# 103_OLED.net
KiCad netlist of a schematic drawn in Altium Designer
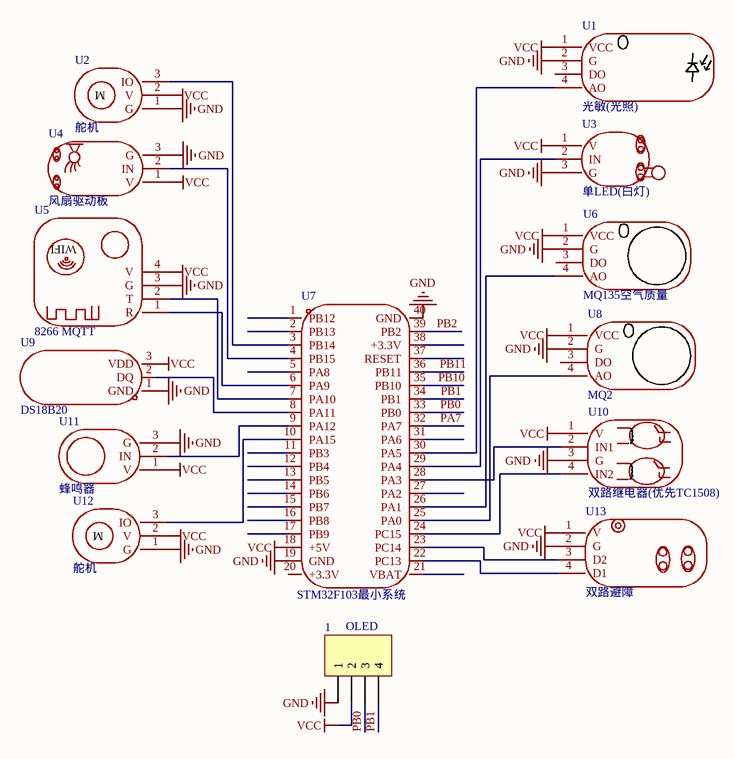
[diagram p0: 103+OLED原理图.SCHDOC]

(export (version "E")
  (design (tool "Eeschema 10.0.6"))
  (components
    (comp (ref "1")
      (value "OLED")
      (footprint "HDR1X4")
      (description "Header, 4-Pin")
      (fields (field (name "PUBLISHER") "Altium Limited"))
      (libsource (lib "Miscellaneous Connectors") (part "Header 4"))
    )
    (comp (ref "U1")
      (value "光敏(光照)")
      (footprint "HDR1X4")
      (description "NCH")
      (libsource (lib "1毕设原理图库") (part "光敏(光照)"))
    )
    (comp (ref "U2")
      (value "舵机")
      (footprint "HDR1X3")
      (description "NBI")
      (libsource (lib "1毕设原理图库") (part "舵机"))
    )
    (comp (ref "U3") (value "单LED(白灯)") (description "NBC") (libsource (lib "1毕设原理图库") (part "单LED(白灯)")))
    (comp (ref "U4")
      (value "风扇驱动板")
      (footprint "HDR1X3")
      (description "NCI")
      (libsource (lib "1毕设原理图库") (part "风扇驱动板"))
    )
    (comp (ref "U5")
      (value "8266 MQTT")
      (footprint "HDR1X4")
      (description "NCB")
      (libsource (lib "1毕设原理图库") (part "8266 MQTT"))
    )
    (comp (ref "U6") (value "MQ135空气质量") (description "NAZM") (libsource (lib "1毕设原理图库") (part "MQ135空气质量")))
    (comp (ref "U7")
      (value "STM32F103最小系统")
      (fields (field (name "MANUFACTURER PART") "LCKFB-DKX-STM32F103C8T6"))
      (libsource (lib "altium-import") (part "root_0_LCKFB-DKX-STM32F103C8T6_"))
    )
    (comp (ref "U8")
      (value "MQ2")
      (footprint "HDR1X4")
      (description "NBE")
      (libsource (lib "1毕设原理图库") (part "MQ2"))
    )
    (comp (ref "U9")
      (value "DS18B20")
      (footprint "HDR1X3")
      (description "NBM")
      (libsource (lib "1毕设原理图库") (part "DS18B20"))
    )
    (comp (ref "U10")
      (value "双路继电器(优先TC1508)")
      (description "NCG")
      (libsource (lib "1毕设原理图库") (part "双路继电器(优先TC1508)"))
    )
    (comp (ref "U11")
      (value "蜂鸣器")
      (footprint "HDR1X3")
      (description "NCD")
      (libsource (lib "1毕设原理图库") (part "蜂鸣器"))
    )
    (comp (ref "U12")
      (value "舵机")
      (footprint "HDR1X3")
      (description "NBI")
      (libsource (lib "") (part "舵机_1"))
    )
    (comp (ref "U13")
      (value "双路避障")
      (footprint "HDR1X4")
      (description "NCL")
      (libsource (lib "1毕设原理图库") (part "双路避障"))
    )
  )
  (nets
    (net (code "1") (name "/PA7") (class "Default")
      (node (ref "U7") (pin "32") (pinfunction "PA7_32") (pintype "passive"))
    )
    (net (code "2") (name "/PB0") (class "Default")
      (node (ref "1") (pin "3") (pinfunction "3_3") (pintype "passive"))
      (node (ref "U7") (pin "33") (pinfunction "PB0_33") (pintype "passive"))
    )
    (net (code "3") (name "/PB1") (class "Default")
      (node (ref "1") (pin "4") (pinfunction "4_4") (pintype "passive"))
      (node (ref "U7") (pin "34") (pinfunction "PB1_34") (pintype "passive"))
    )
    (net (code "4") (name "/PB2") (class "Default")
      (node (ref "U7") (pin "39") (pinfunction "PB2_39") (pintype "passive"))
    )
    (net (code "5") (name "/PB10") (class "Default")
      (node (ref "U7") (pin "35") (pinfunction "PB10_35") (pintype "passive"))
    )
    (net (code "6") (name "/PB11") (class "Default")
      (node (ref "U7") (pin "36") (pinfunction "PB11_36") (pintype "passive"))
    )
    (net (code "7") (name "GND") (class "Default")
      (node (ref "1") (pin "1") (pinfunction "1_1") (pintype "passive"))
      (node (ref "U1") (pin "2") (pinfunction "G_2") (pintype "passive"))
      (node (ref "U10") (pin "3") (pinfunction "G_3") (pintype "passive"))
      (node (ref "U11") (pin "3") (pinfunction "G_3") (pintype "passive"))
      (node (ref "U12") (pin "1") (pinfunction "G_1") (pintype "passive"))
      (node (ref "U13") (pin "2") (pinfunction "G_2") (pintype "passive"))
      (node (ref "U2") (pin "1") (pinfunction "G_1") (pintype "passive"))
      (node (ref "U3") (pin "3") (pinfunction "G_3") (pintype "passive"))
      (node (ref "U4") (pin "3") (pinfunction "G_3") (pintype "passive"))
      (node (ref "U5") (pin "3") (pinfunction "G_3") (pintype "passive"))
      (node (ref "U6") (pin "2") (pinfunction "G_2") (pintype "passive"))
      (node (ref "U7") (pin "19") (pinfunction "GND_19") (pintype "passive"))
      (node (ref "U7") (pin "40") (pinfunction "GND_40") (pintype "passive"))
      (node (ref "U8") (pin "2") (pinfunction "G_2") (pintype "passive"))
      (node (ref "U9") (pin "1") (pinfunction "GND_1") (pintype "passive"))
    )
    (net (code "8") (name "Net-(U1-AO)") (class "Default")
      (node (ref "U1") (pin "4") (pinfunction "AO_4") (pintype "passive"))
      (node (ref "U7") (pin "30") (pinfunction "PA5_30") (pintype "passive"))
    )
    (net (code "9") (name "Net-(U2-IO)") (class "Default")
      (node (ref "U2") (pin "3") (pinfunction "IO_3") (pintype "passive"))
      (node (ref "U7") (pin "3") (pinfunction "PB14_3") (pintype "passive"))
    )
    (net (code "10") (name "Net-(U3-IN)") (class "Default")
      (node (ref "U3") (pin "2") (pinfunction "IN_2") (pintype "passive"))
      (node (ref "U7") (pin "29") (pinfunction "PA4_29") (pintype "passive"))
    )
    (net (code "11") (name "Net-(U4-IN)") (class "Default")
      (node (ref "U4") (pin "2") (pinfunction "IN_2") (pintype "passive"))
      (node (ref "U7") (pin "4") (pinfunction "PB15_4") (pintype "passive"))
    )
    (net (code "12") (name "Net-(U5-R)") (class "Default")
      (node (ref "U5") (pin "1") (pinfunction "R_1") (pintype "passive"))
      (node (ref "U7") (pin "6") (pinfunction "PA9_6") (pintype "passive"))
    )
    (net (code "13") (name "Net-(U5-T)") (class "Default")
      (node (ref "U5") (pin "2") (pinfunction "T_2") (pintype "passive"))
      (node (ref "U7") (pin "7") (pinfunction "PA10_7") (pintype "passive"))
    )
    (net (code "14") (name "Net-(U6-AO)") (class "Default")
      (node (ref "U6") (pin "4") (pinfunction "AO_4") (pintype "passive"))
      (node (ref "U7") (pin "26") (pinfunction "PA1_26") (pintype "passive"))
    )
    (net (code "15") (name "Net-(U7-PA0)") (class "Default")
      (node (ref "U7") (pin "25") (pinfunction "PA0_25") (pintype "passive"))
      (node (ref "U8") (pin "4") (pinfunction "AO_4") (pintype "passive"))
    )
    (net (code "16") (name "Net-(U7-PA11)") (class "Default")
      (node (ref "U7") (pin "8") (pinfunction "PA11_8") (pintype "passive"))
      (node (ref "U9") (pin "2") (pinfunction "DQ_2") (pintype "passive"))
    )
    (net (code "17") (name "Net-(U10-IN1)") (class "Default")
      (node (ref "U10") (pin "2") (pinfunction "IN1_2") (pintype "passive"))
      (node (ref "U7") (pin "28") (pinfunction "PA3_28") (pintype "passive"))
    )
    (net (code "18") (name "Net-(U10-IN2)") (class "Default")
      (node (ref "U10") (pin "4") (pinfunction "IN2_4") (pintype "passive"))
      (node (ref "U7") (pin "24") (pinfunction "PC15_24") (pintype "passive"))
    )
    (net (code "19") (name "Net-(U11-IN)") (class "Default")
      (node (ref "U11") (pin "2") (pinfunction "IN_2") (pintype "passive"))
      (node (ref "U7") (pin "9") (pinfunction "PA12_9") (pintype "passive"))
    )
    (net (code "20") (name "Net-(U12-IO)") (class "Default")
      (node (ref "U12") (pin "3") (pinfunction "IO_3") (pintype "passive"))
      (node (ref "U7") (pin "10") (pinfunction "PA15_10") (pintype "passive"))
    )
    (net (code "21") (name "Net-(U13-D1)") (class "Default")
      (node (ref "U13") (pin "4") (pinfunction "D1_4") (pintype "passive"))
      (node (ref "U7") (pin "22") (pinfunction "PC13_22") (pintype "passive"))
    )
    (net (code "22") (name "Net-(U13-D2)") (class "Default")
      (node (ref "U13") (pin "3") (pinfunction "D2_3") (pintype "passive"))
      (node (ref "U7") (pin "23") (pinfunction "PC14_23") (pintype "passive"))
    )
    (net (code "23") (name "VCC") (class "Default")
      (node (ref "1") (pin "2") (pinfunction "2_2") (pintype "passive"))
      (node (ref "U1") (pin "1") (pinfunction "VCC_1") (pintype "passive"))
      (node (ref "U10") (pin "1") (pinfunction "V_1") (pintype "passive"))
      (node (ref "U11") (pin "1") (pinfunction "V_1") (pintype "passive"))
      (node (ref "U12") (pin "2") (pinfunction "V_2") (pintype "passive"))
      (node (ref "U13") (pin "1") (pinfunction "V_1") (pintype "passive"))
      (node (ref "U2") (pin "2") (pinfunction "V_2") (pintype "passive"))
      (node (ref "U3") (pin "1") (pinfunction "V_1") (pintype "passive"))
      (node (ref "U4") (pin "1") (pinfunction "V_1") (pintype "passive"))
      (node (ref "U5") (pin "4") (pinfunction "V_4") (pintype "passive"))
      (node (ref "U6") (pin "1") (pinfunction "VCC_1") (pintype "passive"))
      (node (ref "U7") (pin "18") (pinfunction "+5V_18") (pintype "passive"))
      (node (ref "U8") (pin "1") (pinfunction "VCC_1") (pintype "passive"))
      (node (ref "U9") (pin "3") (pinfunction "VDD_3") (pintype "passive"))
    )
    (net (code "24") (name "unconnected-(U1-DO-Pad3)") (class "Default")
      (node (ref "U1") (pin "3") (pinfunction "DO_3") (pintype "passive"))
    )
    (net (code "25") (name "unconnected-(U6-DO-Pad3)") (class "Default")
      (node (ref "U6") (pin "3") (pinfunction "DO_3") (pintype "passive"))
    )
    (net (code "26") (name "unconnected-(U7-+3.3V-Pad20)") (class "Default")
      (node (ref "U7") (pin "20") (pinfunction "+3.3V_20") (pintype "passive"))
    )
    (net (code "27") (name "unconnected-(U7-+3.3V-Pad38)") (class "Default")
      (node (ref "U7") (pin "38") (pinfunction "+3.3V_38") (pintype "passive"))
    )
    (net (code "28") (name "unconnected-(U7-PA2-Pad27)") (class "Default")
      (node (ref "U7") (pin "27") (pinfunction "PA2_27") (pintype "passive"))
    )
    (net (code "29") (name "unconnected-(U7-PA6-Pad31)") (class "Default")
      (node (ref "U7") (pin "31") (pinfunction "PA6_31") (pintype "passive"))
    )
    (net (code "30") (name "unconnected-(U7-PA8-Pad5)") (class "Default")
      (node (ref "U7") (pin "5") (pinfunction "PA8_5") (pintype "passive"))
    )
    (net (code "31") (name "unconnected-(U7-PB3-Pad11)") (class "Default")
      (node (ref "U7") (pin "11") (pinfunction "PB3_11") (pintype "passive"))
    )
    (net (code "32") (name "unconnected-(U7-PB4-Pad12)") (class "Default")
      (node (ref "U7") (pin "12") (pinfunction "PB4_12") (pintype "passive"))
    )
    (net (code "33") (name "unconnected-(U7-PB5-Pad13)") (class "Default")
      (node (ref "U7") (pin "13") (pinfunction "PB5_13") (pintype "passive"))
    )
    (net (code "34") (name "unconnected-(U7-PB6-Pad14)") (class "Default")
      (node (ref "U7") (pin "14") (pinfunction "PB6_14") (pintype "passive"))
    )
    (net (code "35") (name "unconnected-(U7-PB7-Pad15)") (class "Default")
      (node (ref "U7") (pin "15") (pinfunction "PB7_15") (pintype "passive"))
    )
    (net (code "36") (name "unconnected-(U7-PB8-Pad16)") (class "Default")
      (node (ref "U7") (pin "16") (pinfunction "PB8_16") (pintype "passive"))
    )
    (net (code "37") (name "unconnected-(U7-PB9-Pad17)") (class "Default")
      (node (ref "U7") (pin "17") (pinfunction "PB9_17") (pintype "passive"))
    )
    (net (code "38") (name "unconnected-(U7-PB12-Pad1)") (class "Default")
      (node (ref "U7") (pin "1") (pinfunction "PB12_1") (pintype "passive"))
    )
    (net (code "39") (name "unconnected-(U7-PB13-Pad2)") (class "Default")
      (node (ref "U7") (pin "2") (pinfunction "PB13_2") (pintype "passive"))
    )
    (net (code "40") (name "unconnected-(U7-RESET-Pad37)") (class "Default")
      (node (ref "U7") (pin "37") (pinfunction "RESET_37") (pintype "passive"))
    )
    (net (code "41") (name "unconnected-(U7-VBAT-Pad21)") (class "Default")
      (node (ref "U7") (pin "21") (pinfunction "VBAT_21") (pintype "passive"))
    )
    (net (code "42") (name "unconnected-(U8-DO-Pad3)") (class "Default")
      (node (ref "U8") (pin "3") (pinfunction "DO_3") (pintype "passive"))
    )
  )
)
